# Gyro.net
KiCad netlist of a schematic drawn in Altium Designer
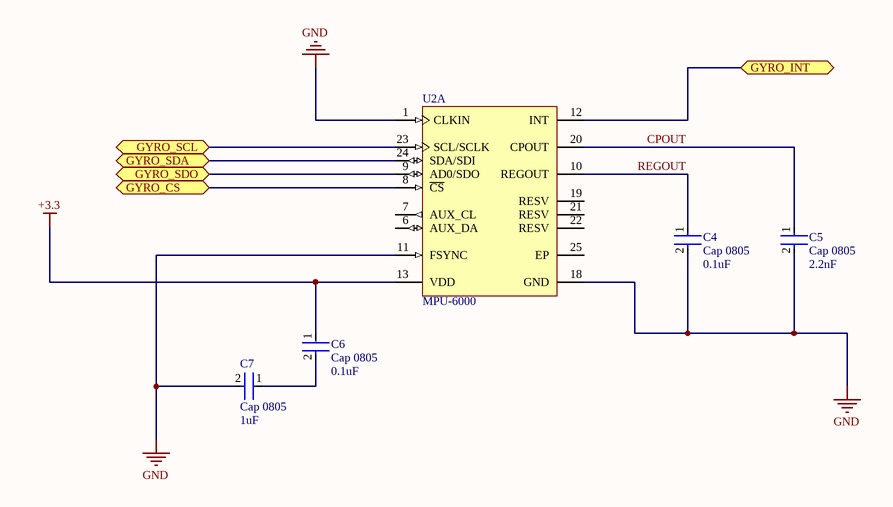
[diagram p0: Gyro.SchDoc]

(export (version "E")
  (design (tool "Eeschema 10.0.6"))
  (components
    (comp (ref "C4")
      (value "Cap 0805")
      (footprint "FP-GRM216-0_1-IPC_C")
      (description "Capacitor")
      (fields (field (name "ALTIUM_VALUE") "0.1uF"))
      (libsource (lib "Altium Content Vault") (part "236180d848d6139a670b325ea6854c9"))
    )
    (comp (ref "C5")
      (value "Cap 0805")
      (footprint "FP-GRM216-0_1-IPC_C")
      (description "Capacitor")
      (fields (field (name "ALTIUM_VALUE") "2.2nF"))
      (libsource (lib "Altium Content Vault") (part "236180d848d6139a670b325ea6854c9"))
    )
    (comp (ref "C6")
      (value "Cap 0805")
      (footprint "FP-GRM216-0_1-IPC_C")
      (description "Capacitor")
      (fields (field (name "ALTIUM_VALUE") "0.1uF"))
      (libsource (lib "Altium Content Vault") (part "236180d848d6139a670b325ea6854c9"))
    )
    (comp (ref "C7")
      (value "Cap 0805")
      (footprint "FP-GRM216-0_1-IPC_C")
      (description "Capacitor")
      (fields (field (name "ALTIUM_VALUE") "1uF"))
      (libsource (lib "Altium Content Vault") (part "236180d848d6139a670b325ea6854c9"))
    )
    (comp (ref "U2")
      (value "MPU-6000")
      (footprint "INSE-QFN-24_V")
      (fields (field (name "MANUFACTURER") "InvenSense"))
      (libsource (lib "Altium Content Vault") (part "INSE-MPU-6000"))
    )
  )
  (nets
    (net (code "1") (name "+3.3") (class "Default")
      (node (ref "C6") (pin "1") (pinfunction "1_1") (pintype "passive"))
      (node (ref "U2") (pin "13") (pinfunction "VDD_13") (pintype "power_in"))
    )
    (net (code "2") (name "/CPOUT") (class "Default")
      (node (ref "C5") (pin "1") (pinfunction "1_1") (pintype "passive"))
      (node (ref "U2") (pin "20") (pinfunction "CPOUT_20") (pintype "passive"))
    )
    (net (code "3") (name "/GYRO_CS") (class "Default")
      (node (ref "U2") (pin "8") (pinfunction "~{CS}_8") (pintype "input"))
    )
    (net (code "4") (name "/GYRO_INT") (class "Default")
      (node (ref "U2") (pin "12") (pinfunction "INT_12") (pintype "open_collector"))
    )
    (net (code "5") (name "/GYRO_SCL") (class "Default")
      (node (ref "U2") (pin "23") (pinfunction "SCL/SCLK_23") (pintype "input"))
    )
    (net (code "6") (name "/GYRO_SDA") (class "Default")
      (node (ref "U2") (pin "24") (pinfunction "SDA/SDI_24") (pintype "bidirectional"))
    )
    (net (code "7") (name "/GYRO_SDO") (class "Default")
      (node (ref "U2") (pin "9") (pinfunction "AD0/SDO_9") (pintype "bidirectional"))
    )
    (net (code "8") (name "/REGOUT") (class "Default")
      (node (ref "C4") (pin "1") (pinfunction "1_1") (pintype "passive"))
      (node (ref "U2") (pin "10") (pinfunction "REGOUT_10") (pintype "passive"))
    )
    (net (code "9") (name "GND") (class "Default")
      (node (ref "C4") (pin "2") (pinfunction "2_2") (pintype "passive"))
      (node (ref "C5") (pin "2") (pinfunction "2_2") (pintype "passive"))
      (node (ref "C7") (pin "2") (pinfunction "2_2") (pintype "passive"))
      (node (ref "U2") (pin "1") (pinfunction "CLKIN_1") (pintype "input"))
      (node (ref "U2") (pin "11") (pinfunction "FSYNC_11") (pintype "input"))
      (node (ref "U2") (pin "18") (pinfunction "GND_18") (pintype "power_in"))
    )
    (net (code "10") (name "Net-(C6-Pad2)") (class "Default")
      (node (ref "C6") (pin "2") (pinfunction "2_2") (pintype "passive"))
      (node (ref "C7") (pin "1") (pinfunction "1_1") (pintype "passive"))
    )
    (net (code "11") (name "unconnected-(U2A-AUX_CL-Pad7)") (class "Default")
      (node (ref "U2") (pin "7") (pinfunction "AUX_CL_7") (pintype "output"))
    )
    (net (code "12") (name "unconnected-(U2A-AUX_DA-Pad6)") (class "Default")
      (node (ref "U2") (pin "6") (pinfunction "AUX_DA_6") (pintype "bidirectional"))
    )
    (net (code "13") (name "unconnected-(U2A-EP-Pad25)") (class "Default")
      (node (ref "U2") (pin "25") (pinfunction "EP_25") (pintype "passive"))
    )
    (net (code "14") (name "unconnected-(U2A-RESV-Pad19)") (class "Default")
      (node (ref "U2") (pin "19") (pinfunction "RESV_19") (pintype "passive"))
    )
    (net (code "15") (name "unconnected-(U2A-RESV-Pad21)") (class "Default")
      (node (ref "U2") (pin "21") (pinfunction "RESV_21") (pintype "passive"))
    )
    (net (code "16") (name "unconnected-(U2A-RESV-Pad22)") (class "Default")
      (node (ref "U2") (pin "22") (pinfunction "RESV_22") (pintype "passive"))
    )
  )
)
